# Clock.net
KiCad netlist of a schematic drawn in EAGLE
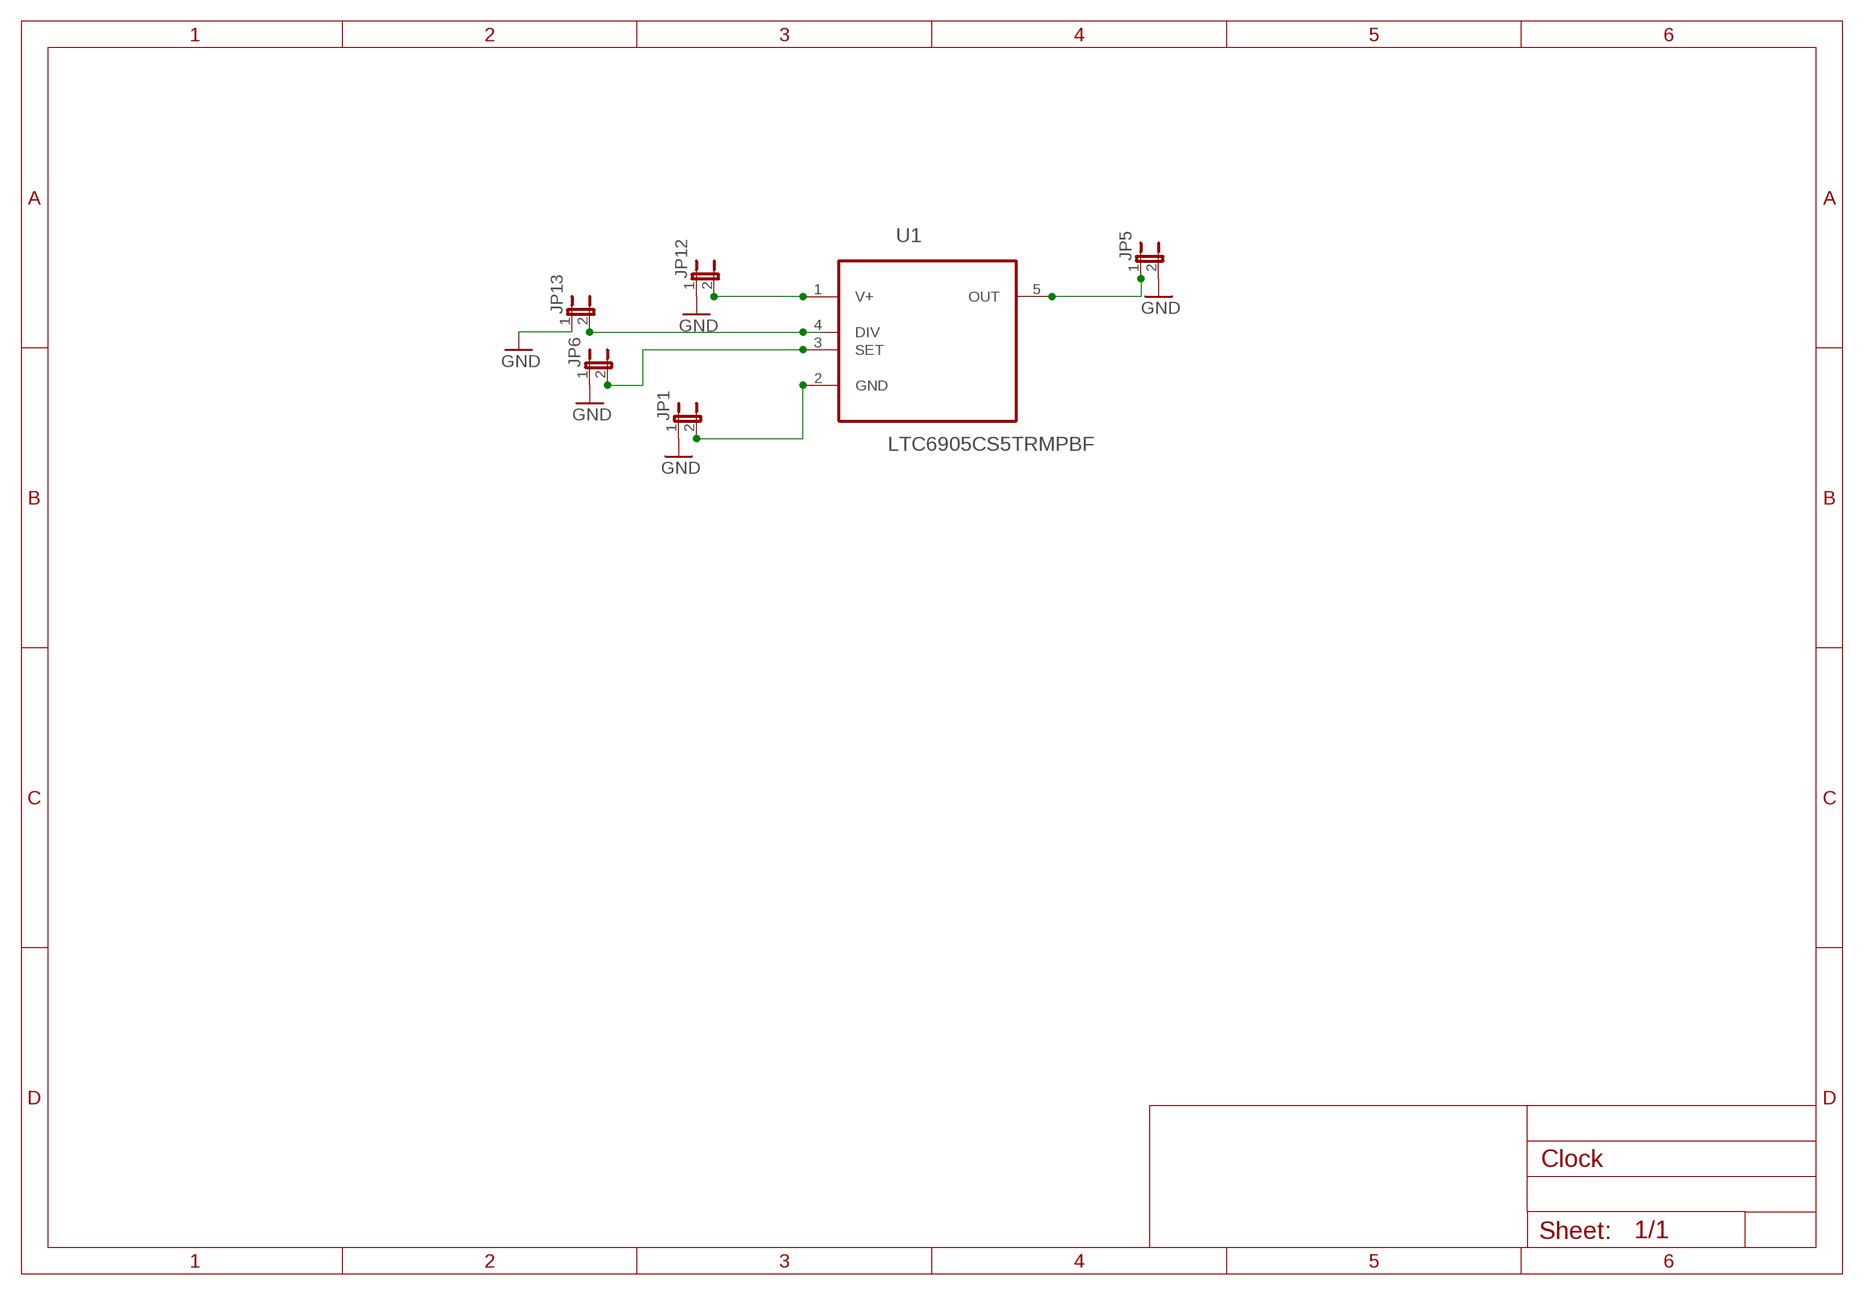
[diagram p0: schematic, sheet 1]

(export (version "E")
  (design (tool "Eeschema 10.0.6"))
  (components
    (comp (ref "JP1")
      (value "JP1E")
      (footprint "eagle-import:JP1")
      (libsource (lib "eagle-import") (part "JP1E"))
    )
    (comp (ref "JP5")
      (value "JP1E")
      (footprint "eagle-import:JP1")
      (libsource (lib "eagle-import") (part "JP1E"))
    )
    (comp (ref "JP6")
      (value "JP1E")
      (footprint "eagle-import:JP1")
      (libsource (lib "eagle-import") (part "JP1E"))
    )
    (comp (ref "JP12")
      (value "JP1E")
      (footprint "eagle-import:JP1")
      (libsource (lib "eagle-import") (part "JP1E"))
    )
    (comp (ref "JP13")
      (value "JP1E")
      (footprint "eagle-import:JP1")
      (libsource (lib "eagle-import") (part "JP1E"))
    )
    (comp (ref "U1")
      (value "LTC6905CS5TRMPBF")
      (footprint "eagle-import:SOT95P280X100-5N")
      (fields (field (name "MPN") "LTC6905CS5#TRMPBF"))
      (libsource (lib "eagle-import") (part "LTC6905CS5TRMPBF"))
    )
  )
  (nets
    (net (code "1") (name "GND") (class "Default")
      (node (ref "JP1") (pin "1") (pinfunction "1_1") (pintype "passive"))
      (node (ref "JP12") (pin "1") (pinfunction "1_1") (pintype "passive"))
      (node (ref "JP13") (pin "1") (pinfunction "1_1") (pintype "passive"))
      (node (ref "JP5") (pin "2") (pinfunction "2_2") (pintype "passive"))
      (node (ref "JP6") (pin "1") (pinfunction "1_1") (pintype "passive"))
    )
    (net (code "2") (name "Net-(U1-DIV)") (class "Default")
      (node (ref "JP13") (pin "2") (pinfunction "2_2") (pintype "passive"))
      (node (ref "U1") (pin "4") (pinfunction "DIV_4") (pintype "input"))
    )
    (net (code "3") (name "Net-(U1-GND)") (class "Default")
      (node (ref "JP1") (pin "2") (pinfunction "2_2") (pintype "passive"))
      (node (ref "U1") (pin "2") (pinfunction "GND_2") (pintype "passive"))
    )
    (net (code "4") (name "Net-(U1-OUT)") (class "Default")
      (node (ref "JP5") (pin "1") (pinfunction "1_1") (pintype "passive"))
      (node (ref "U1") (pin "5") (pinfunction "OUT_5") (pintype "output"))
    )
    (net (code "5") (name "Net-(U1-SET)") (class "Default")
      (node (ref "JP6") (pin "2") (pinfunction "2_2") (pintype "passive"))
      (node (ref "U1") (pin "3") (pinfunction "SET_3") (pintype "input"))
    )
    (net (code "6") (name "Net-(U1-V+)") (class "Default")
      (node (ref "JP12") (pin "2") (pinfunction "2_2") (pintype "passive"))
      (node (ref "U1") (pin "1") (pinfunction "V+_1") (pintype "power_in"))
    )
  )
)
